# Out.net
KiCad netlist of a schematic drawn in Altium Designer
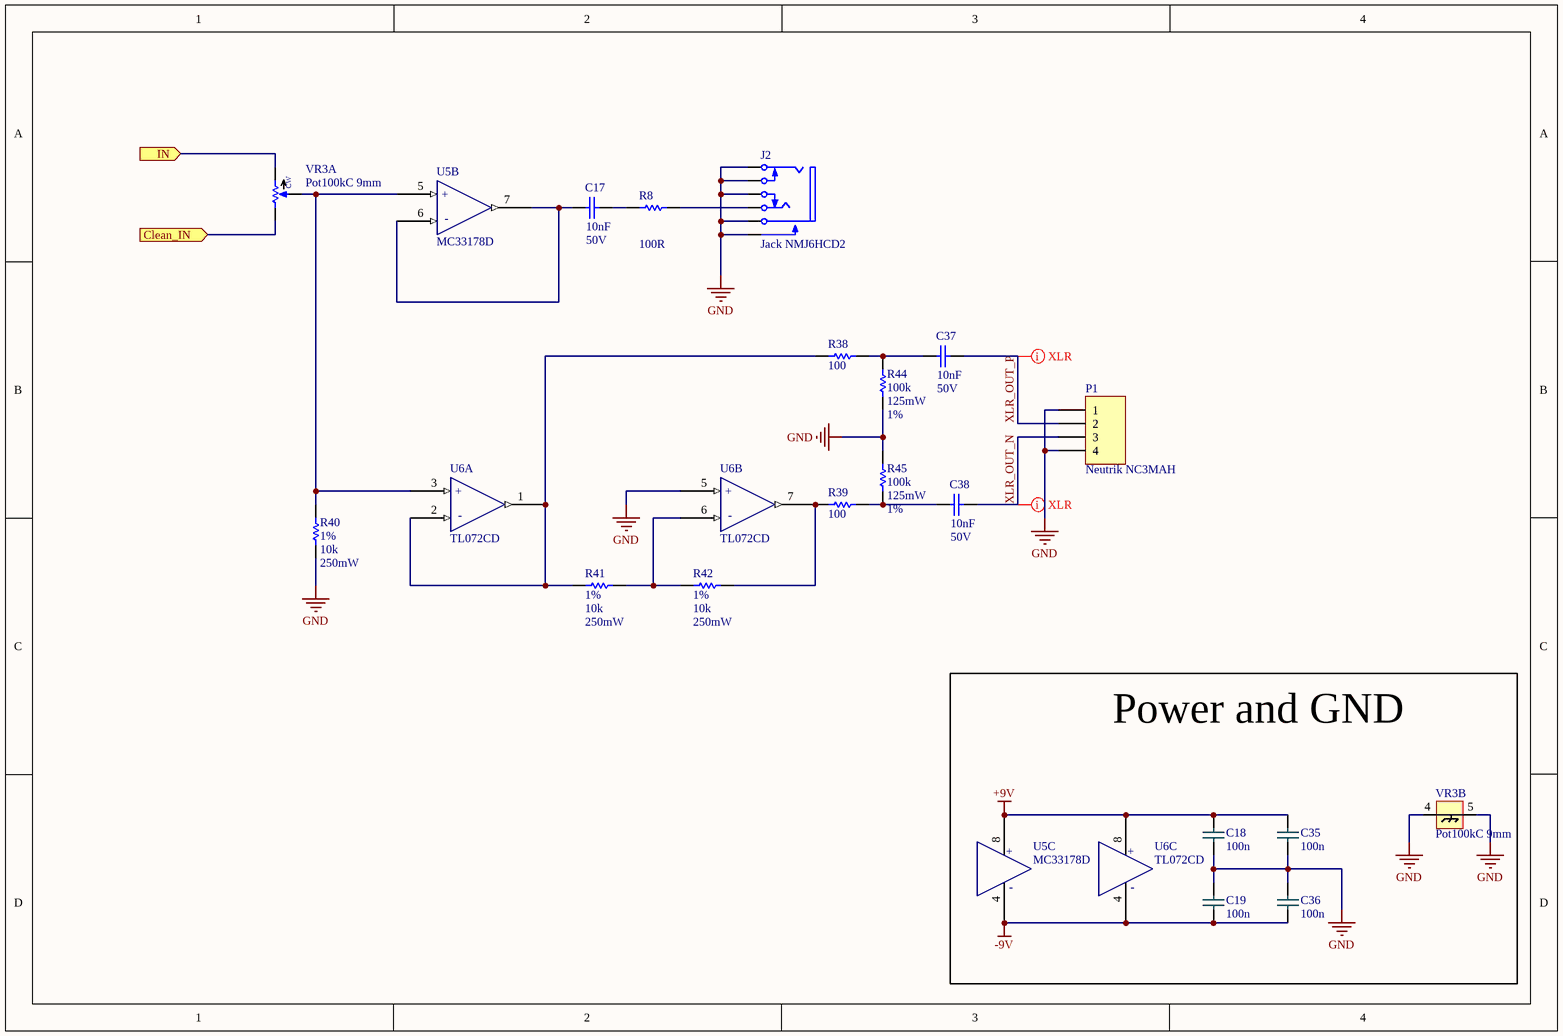
[diagram p0: Out.SchDoc]

(export (version "E")
  (design (tool "Eeschema 10.0.6"))
  (components
    (comp (ref "C17")
      (value "Cap 10nF 0805 C0G")
      (footprint "0805-CAP")
      (description "Cap 10nF 0805 C0G 50V +-5%")
      (fields (field (name "CAPACITANCE") "10nF") (field (name "RATED VOLTAGE") "50V"))
      (libsource (lib "Darkglass Electronics") (part "Capacitor Non-polarized"))
    )
    (comp (ref "C18")
      (value "100n")
      (footprint "0805-CAP")
      (description "0.1uF 25volts C0G 5%")
      (fields
        (field (name "MOUSER PART") "81-GRM31C5C1E104JA01")
        (field (name "Comment") "Cap 0805 100nF 4")
        (field (name "PUBLISHER") "Altium Limited")
      )
      (libsource (lib "Darkglass Electronics") (part "Capacitor NP"))
    )
    (comp (ref "C19")
      (value "100n")
      (footprint "0805-CAP")
      (description "0.1uF 25volts C0G 5%")
      (fields
        (field (name "MOUSER PART") "81-GRM31C5C1E104JA01")
        (field (name "Comment") "Cap 0805 100nF 4")
        (field (name "PUBLISHER") "Altium Limited")
      )
      (libsource (lib "Darkglass Electronics") (part "Capacitor NP"))
    )
    (comp (ref "C35")
      (value "100n")
      (footprint "0805-CAP")
      (description "0.1uF 25volts C0G 5%")
      (fields
        (field (name "MOUSER PART") "81-GRM31C5C1E104JA01")
        (field (name "Comment") "Cap 0805 100nF 4")
        (field (name "PUBLISHER") "Altium Limited")
      )
      (libsource (lib "Darkglass Electronics") (part "Capacitor NP"))
    )
    (comp (ref "C36")
      (value "100n")
      (footprint "0805-CAP")
      (description "0.1uF 25volts C0G 5%")
      (fields
        (field (name "MOUSER PART") "81-GRM31C5C1E104JA01")
        (field (name "Comment") "Cap 0805 100nF 4")
        (field (name "PUBLISHER") "Altium Limited")
      )
      (libsource (lib "Darkglass Electronics") (part "Capacitor NP"))
    )
    (comp (ref "C37")
      (value "Cap 10nF 0805 C0G")
      (footprint "0805-CAP")
      (description "Cap 10nF 0805 C0G 50V +-5%")
      (fields (field (name "CAPACITANCE") "10nF") (field (name "RATED VOLTAGE") "50V"))
      (libsource (lib "Darkglass Electronics") (part "Capacitor Non-polarized"))
    )
    (comp (ref "C38")
      (value "Cap 10nF 0805 C0G")
      (footprint "0805-CAP")
      (description "Cap 10nF 0805 C0G 50V +-5%")
      (fields (field (name "CAPACITANCE") "10nF") (field (name "RATED VOLTAGE") "50V"))
      (libsource (lib "Darkglass Electronics") (part "Capacitor Non-polarized"))
    )
    (comp (ref "J2")
      (value "Jack NMJ6HCD2")
      (footprint "Neutrik Jack metal nut")
      (description "Jack 1/4 stereo switched - PCBH - chrome nut")
      (fields (field (name "MANUFACTURER") "Neutrik") (field (name "DARKGLASS PART") "D00-0011"))
      (libsource (lib "") (part "Symbol_2"))
    )
    (comp (ref "P1")
      (value "Neutrik NC3MAH")
      (footprint "NC3MAH-0 XLR")
      (description "Neutrik XLR NC3MAH")
      (fields (field (name "MANUFACTURER PART NUMBER") "NC3MAH") (field (name "DARKGLASS PART") "D00-0015"))
      (libsource (lib "Darkglass Electronics") (part "Symbol"))
    )
    (comp (ref "R8")
      (value "Res 0805 100R 1%")
      (footprint "0805-RES")
      (description "100ohm, 125mW, 1%, thin film")
      (fields
        (field (name "RESISTANCE") "100R")
        (field (name "TOLERANCE") "1%")
        (field (name "PUBLISHER") "Altium Limited")
      )
      (libsource (lib "Darkglass Electronics") (part "RES"))
    )
    (comp (ref "R38")
      (value "Res 100R 1% 1206")
      (footprint "1206-RES")
      (description "Resistor 100R +-1% 1206 Thin film 0.25W +-50ppm/°C")
      (fields (field (name "POWER") "250mW") (field (name "RESISTANCE") "100"))
      (libsource (lib "Darkglass Electronics") (part "Resistor"))
    )
    (comp (ref "R39")
      (value "Res 100R 1% 1206")
      (footprint "1206-RES")
      (description "Resistor 100R +-1% 1206 Thin film 0.25W +-50ppm/°C")
      (fields (field (name "POWER") "250mW") (field (name "RESISTANCE") "100"))
      (libsource (lib "Darkglass Electronics") (part "Resistor"))
    )
    (comp (ref "R40")
      (value "Res 10k 1% 1206")
      (footprint "1206-RES")
      (description "Resistor 10k +-1% 1206 Thin film 0.25W +-50ppm/°C")
      (fields
        (field (name "TOLERANCE (+-)") "1%")
        (field (name "RESISTANCE") "10k")
        (field (name "POWER") "250mW")
      )
      (libsource (lib "Darkglass Electronics") (part "Resistor"))
    )
    (comp (ref "R41")
      (value "Res 10k 1% 1206")
      (footprint "1206-RES")
      (description "Resistor 10k +-1% 1206 Thin film 0.25W +-50ppm/°C")
      (fields
        (field (name "TOLERANCE (+-)") "1%")
        (field (name "RESISTANCE") "10k")
        (field (name "POWER") "250mW")
      )
      (libsource (lib "Darkglass Electronics") (part "Resistor"))
    )
    (comp (ref "R42")
      (value "Res 10k 1% 1206")
      (footprint "1206-RES")
      (description "Resistor 10k +-1% 1206 Thin film 0.25W +-50ppm/°C")
      (fields
        (field (name "TOLERANCE (+-)") "1%")
        (field (name "RESISTANCE") "10k")
        (field (name "POWER") "250mW")
      )
      (libsource (lib "Darkglass Electronics") (part "Resistor"))
    )
    (comp (ref "R44")
      (value "Res 100k 1% 0805")
      (footprint "0805-RES")
      (description "Resistor 100k +-1% 0805 Thin film 0.125W +-50ppm/°C")
      (fields
        (field (name "RESISTANCE") "100k")
        (field (name "POWER") "125mW")
        (field (name "TOLERANCE (+-)") "1%")
      )
      (libsource (lib "Darkglass Electronics") (part "Resistor"))
    )
    (comp (ref "R45")
      (value "Res 100k 1% 0805")
      (footprint "0805-RES")
      (description "Resistor 100k +-1% 0805 Thin film 0.125W +-50ppm/°C")
      (fields
        (field (name "RESISTANCE") "100k")
        (field (name "POWER") "125mW")
        (field (name "TOLERANCE (+-)") "1%")
      )
      (libsource (lib "Darkglass Electronics") (part "Resistor"))
    )
    (comp (ref "U5")
      (value "MC33178D")
      (footprint "SOIC8-127P600X175-8N")
      (description "IC OPAMP GP 5MHZ 8SOIC")
      (fields (field (name "MANUFACTURER") "ON Semiconductor") (field (name "MOUSER PART") "863-MC33178DG"))
      (libsource (lib "") (part "Symbol_1"))
    )
    (comp (ref "U6")
      (value "TL072CD")
      (footprint "SOIC8-127P600X175-8N")
      (description "Operational Amplifiers - Op Amps Dual Low Noise JFET SOIC8")
      (libsource (lib "Darkglass Electronics") (part "TL072CD"))
    )
    (comp (ref "VR3")
      (value "Pot100kC 9mm")
      (footprint "LJV 9mm pot")
      (description "LJV 9mm pot")
      (fields (field (name "DARKGLASS PART") "D00-0002"))
      (libsource (lib "") (part "Pot100kC 9mm_1"))
    )
  )
  (nets
    (net (code "1") (name "+9V") (class "Default")
      (node (ref "C18") (pin "2") (pinfunction "2_2") (pintype "passive"))
      (node (ref "C35") (pin "2") (pinfunction "2_2") (pintype "passive"))
      (node (ref "U5") (pin "8") (pinfunction "8_8") (pintype "power_in"))
      (node (ref "U6") (pin "8") (pinfunction "V+_8") (pintype "power_in"))
    )
    (net (code "2") (name "-9V") (class "Default")
      (node (ref "C19") (pin "1") (pinfunction "1_1") (pintype "passive"))
      (node (ref "C36") (pin "1") (pinfunction "1_1") (pintype "passive"))
      (node (ref "U5") (pin "4") (pinfunction "4_4") (pintype "power_in"))
      (node (ref "U6") (pin "4") (pinfunction "V-_4") (pintype "power_in"))
    )
    (net (code "3") (name "/Clean_IN") (class "Default")
      (node (ref "VR3") (pin "1") (pinfunction "CCWPIN_1") (pintype "passive"))
    )
    (net (code "4") (name "/IN") (class "Default")
      (node (ref "VR3") (pin "3") (pinfunction "CWPIN_3") (pintype "passive"))
    )
    (net (code "5") (name "/XLR_OUT_N") (class "Default")
      (node (ref "C38") (pin "2") (pinfunction "2_2") (pintype "passive"))
      (node (ref "P1") (pin "3") (pinfunction "3_3") (pintype "passive"))
    )
    (net (code "6") (name "/XLR_OUT_P") (class "Default")
      (node (ref "C37") (pin "2") (pinfunction "2_2") (pintype "passive"))
      (node (ref "P1") (pin "2") (pinfunction "2_2") (pintype "passive"))
    )
    (net (code "7") (name "GND") (class "Default")
      (node (ref "C18") (pin "1") (pinfunction "1_1") (pintype "passive"))
      (node (ref "C19") (pin "2") (pinfunction "2_2") (pintype "passive"))
      (node (ref "C35") (pin "1") (pinfunction "1_1") (pintype "passive"))
      (node (ref "C36") (pin "2") (pinfunction "2_2") (pintype "passive"))
      (node (ref "J2") (pin "1") (pinfunction "1_1") (pintype "passive"))
      (node (ref "J2") (pin "2") (pinfunction "2_2") (pintype "passive"))
      (node (ref "J2") (pin "4") (pinfunction "4_4") (pintype "passive"))
      (node (ref "J2") (pin "5") (pinfunction "5_5") (pintype "passive"))
      (node (ref "J2") (pin "6") (pinfunction "6_6") (pintype "passive"))
      (node (ref "P1") (pin "1") (pinfunction "1_1") (pintype "passive"))
      (node (ref "P1") (pin "4") (pinfunction "4_4") (pintype "passive"))
      (node (ref "R40") (pin "1") (pinfunction "1_1") (pintype "passive"))
      (node (ref "R44") (pin "1") (pinfunction "1_1") (pintype "passive"))
      (node (ref "R45") (pin "2") (pinfunction "2_2") (pintype "passive"))
      (node (ref "U6") (pin "5") (pinfunction "IN+_5") (pintype "input"))
      (node (ref "VR3") (pin "4") (pinfunction "4_4") (pintype "passive"))
      (node (ref "VR3") (pin "5") (pinfunction "5_5") (pintype "passive"))
    )
    (net (code "8") (name "Net-(C17-Pad1)") (class "Default")
      (node (ref "C17") (pin "1") (pinfunction "1_1") (pintype "passive"))
      (node (ref "U5") (pin "6") (pinfunction "6_6") (pintype "input"))
      (node (ref "U5") (pin "7") (pinfunction "7_7") (pintype "output"))
    )
    (net (code "9") (name "Net-(C17-Pad2)") (class "Default")
      (node (ref "C17") (pin "2") (pinfunction "2_2") (pintype "passive"))
      (node (ref "R8") (pin "2") (pinfunction "2_2") (pintype "passive"))
    )
    (net (code "10") (name "Net-(C37-Pad1)") (class "Default")
      (node (ref "C37") (pin "1") (pinfunction "1_1") (pintype "passive"))
      (node (ref "R38") (pin "1") (pinfunction "1_1") (pintype "passive"))
      (node (ref "R44") (pin "2") (pinfunction "2_2") (pintype "passive"))
    )
    (net (code "11") (name "Net-(C38-Pad1)") (class "Default")
      (node (ref "C38") (pin "1") (pinfunction "1_1") (pintype "passive"))
      (node (ref "R39") (pin "1") (pinfunction "1_1") (pintype "passive"))
      (node (ref "R45") (pin "1") (pinfunction "1_1") (pintype "passive"))
    )
    (net (code "12") (name "Net-(J2-Pad3)") (class "Default")
      (node (ref "J2") (pin "3") (pinfunction "3_3") (pintype "passive"))
      (node (ref "R8") (pin "1") (pinfunction "1_1") (pintype "passive"))
    )
    (net (code "13") (name "Net-(R39-Pad2)") (class "Default")
      (node (ref "R39") (pin "2") (pinfunction "2_2") (pintype "passive"))
      (node (ref "R42") (pin "2") (pinfunction "2_2") (pintype "passive"))
      (node (ref "U6") (pin "7") (pinfunction "7_7") (pintype "output"))
    )
    (net (code "14") (name "Net-(U6A-IN+)") (class "Default")
      (node (ref "R40") (pin "2") (pinfunction "2_2") (pintype "passive"))
      (node (ref "U5") (pin "5") (pinfunction "5_5") (pintype "input"))
      (node (ref "U6") (pin "3") (pinfunction "IN+_3") (pintype "input"))
      (node (ref "VR3") (pin "2") (pinfunction "WIPER_2") (pintype "passive"))
    )
    (net (code "15") (name "Net-(U6A-IN-)") (class "Default")
      (node (ref "R38") (pin "2") (pinfunction "2_2") (pintype "passive"))
      (node (ref "R41") (pin "1") (pinfunction "1_1") (pintype "passive"))
      (node (ref "U6") (pin "1") (pinfunction "OUT_1") (pintype "output"))
      (node (ref "U6") (pin "2") (pinfunction "IN-_2") (pintype "input"))
    )
    (net (code "16") (name "Net-(U6B-IN-)") (class "Default")
      (node (ref "R41") (pin "2") (pinfunction "2_2") (pintype "passive"))
      (node (ref "R42") (pin "1") (pinfunction "1_1") (pintype "passive"))
      (node (ref "U6") (pin "6") (pinfunction "IN-_6") (pintype "input"))
    )
  )
)
